# 2025_08_22_io.net
KiCad netlist of a schematic drawn in EasyEDA Pro
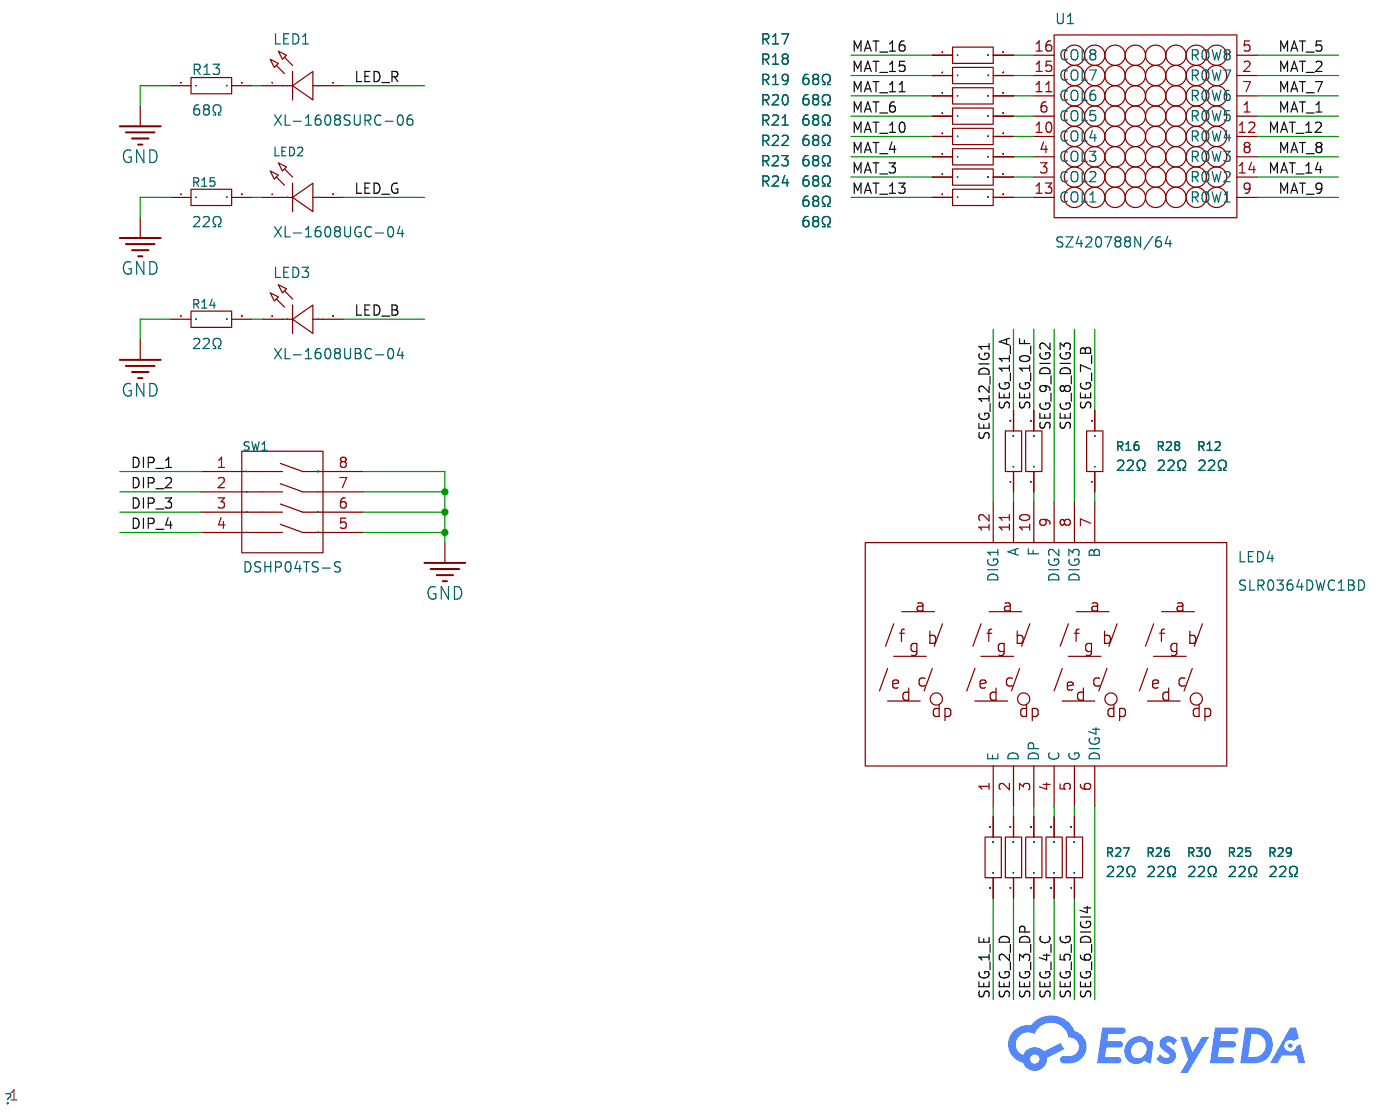
[diagram p0: schematic sheet]

(export (version "E")
  (design (tool "Eeschema 10.0.6"))
  (components
    (comp (ref "LED1")
      (value "XL-1608SURC-06")
      (footprint "easyedapro:LED0603-RD_RED")
      (fields (field (name "Manufacturer") "XINGLIGHT(成兴光)"))
      (libsource (lib "easyedapro") (part "XL-1608SURC-06"))
    )
    (comp (ref "LED2")
      (value "XL-1608UGC-04")
      (footprint "easyedapro:LED0603-RD_GREEN")
      (fields (field (name "Manufacturer") "XINGLIGHT(成兴光)"))
      (libsource (lib "easyedapro") (part "XL-1608UGC-04"))
    )
    (comp (ref "LED3")
      (value "XL-1608UBC-04")
      (footprint "easyedapro:LED0603-RD_BLUE")
      (fields (field (name "Manufacturer") "XINGLIGHT(成兴光)"))
      (libsource (lib "easyedapro") (part "XL-1608UBC-04"))
    )
    (comp (ref "LED4")
      (value "SLR0364DWC1BD")
      (footprint "easyedapro:LED-SEG-TH_12P-L30.0-W14.0-P2.54-S10.16-BL")
      (fields (field (name "Manufacturer") "SUNLIGHT(光华)"))
      (libsource (lib "easyedapro") (part "SLR0364DWC1BD_C2913068"))
    )
    (comp (ref "R12")
      (value "22Ω")
      (footprint "easyedapro:R0402")
      (fields
        (field (name "Manufacturer Part") "0402WGF220JTCE")
        (field (name "Manufacturer") "UNI-ROYAL(厚声)")
      )
      (libsource (lib "easyedapro") (part "0402WGF220JTCE"))
    )
    (comp (ref "R13")
      (value "68Ω")
      (footprint "easyedapro:R0402")
      (fields (field (name "Manufacturer Part") "RC0402FR-0768RL") (field (name "Manufacturer") "YAGEO(国巨)"))
      (libsource (lib "easyedapro") (part "RC0402FR-0768RL"))
    )
    (comp (ref "R14")
      (value "22Ω")
      (footprint "easyedapro:R0402")
      (fields
        (field (name "Manufacturer Part") "0402WGF220JTCE")
        (field (name "Manufacturer") "UNI-ROYAL(厚声)")
      )
      (libsource (lib "easyedapro") (part "0402WGF220JTCE"))
    )
    (comp (ref "R15")
      (value "22Ω")
      (footprint "easyedapro:R0402")
      (fields
        (field (name "Manufacturer Part") "0402WGF220JTCE")
        (field (name "Manufacturer") "UNI-ROYAL(厚声)")
      )
      (libsource (lib "easyedapro") (part "0402WGF220JTCE"))
    )
    (comp (ref "R16")
      (value "22Ω")
      (footprint "easyedapro:R0402")
      (fields
        (field (name "Manufacturer Part") "0402WGF220JTCE")
        (field (name "Manufacturer") "UNI-ROYAL(厚声)")
      )
      (libsource (lib "easyedapro") (part "0402WGF220JTCE"))
    )
    (comp (ref "R17")
      (value "68Ω")
      (footprint "easyedapro:R0402")
      (fields (field (name "Manufacturer Part") "RC0402FR-0768RL") (field (name "Manufacturer") "YAGEO(国巨)"))
      (libsource (lib "easyedapro") (part "RC0402FR-0768RL"))
    )
    (comp (ref "R18")
      (value "68Ω")
      (footprint "easyedapro:R0402")
      (fields (field (name "Manufacturer Part") "RC0402FR-0768RL") (field (name "Manufacturer") "YAGEO(国巨)"))
      (libsource (lib "easyedapro") (part "RC0402FR-0768RL"))
    )
    (comp (ref "R19")
      (value "68Ω")
      (footprint "easyedapro:R0402")
      (fields (field (name "Manufacturer Part") "RC0402FR-0768RL") (field (name "Manufacturer") "YAGEO(国巨)"))
      (libsource (lib "easyedapro") (part "RC0402FR-0768RL"))
    )
    (comp (ref "R20")
      (value "68Ω")
      (footprint "easyedapro:R0402")
      (fields (field (name "Manufacturer Part") "RC0402FR-0768RL") (field (name "Manufacturer") "YAGEO(国巨)"))
      (libsource (lib "easyedapro") (part "RC0402FR-0768RL"))
    )
    (comp (ref "R21")
      (value "68Ω")
      (footprint "easyedapro:R0402")
      (fields (field (name "Manufacturer Part") "RC0402FR-0768RL") (field (name "Manufacturer") "YAGEO(国巨)"))
      (libsource (lib "easyedapro") (part "RC0402FR-0768RL"))
    )
    (comp (ref "R22")
      (value "68Ω")
      (footprint "easyedapro:R0402")
      (fields (field (name "Manufacturer Part") "RC0402FR-0768RL") (field (name "Manufacturer") "YAGEO(国巨)"))
      (libsource (lib "easyedapro") (part "RC0402FR-0768RL"))
    )
    (comp (ref "R23")
      (value "68Ω")
      (footprint "easyedapro:R0402")
      (fields (field (name "Manufacturer Part") "RC0402FR-0768RL") (field (name "Manufacturer") "YAGEO(国巨)"))
      (libsource (lib "easyedapro") (part "RC0402FR-0768RL"))
    )
    (comp (ref "R24")
      (value "68Ω")
      (footprint "easyedapro:R0402")
      (fields (field (name "Manufacturer Part") "RC0402FR-0768RL") (field (name "Manufacturer") "YAGEO(国巨)"))
      (libsource (lib "easyedapro") (part "RC0402FR-0768RL"))
    )
    (comp (ref "R25")
      (value "22Ω")
      (footprint "easyedapro:R0402")
      (fields
        (field (name "Manufacturer Part") "0402WGF220JTCE")
        (field (name "Manufacturer") "UNI-ROYAL(厚声)")
      )
      (libsource (lib "easyedapro") (part "0402WGF220JTCE"))
    )
    (comp (ref "R26")
      (value "22Ω")
      (footprint "easyedapro:R0402")
      (fields
        (field (name "Manufacturer Part") "0402WGF220JTCE")
        (field (name "Manufacturer") "UNI-ROYAL(厚声)")
      )
      (libsource (lib "easyedapro") (part "0402WGF220JTCE"))
    )
    (comp (ref "R27")
      (value "22Ω")
      (footprint "easyedapro:R0402")
      (fields
        (field (name "Manufacturer Part") "0402WGF220JTCE")
        (field (name "Manufacturer") "UNI-ROYAL(厚声)")
      )
      (libsource (lib "easyedapro") (part "0402WGF220JTCE"))
    )
    (comp (ref "R28")
      (value "22Ω")
      (footprint "easyedapro:R0402")
      (fields
        (field (name "Manufacturer Part") "0402WGF220JTCE")
        (field (name "Manufacturer") "UNI-ROYAL(厚声)")
      )
      (libsource (lib "easyedapro") (part "0402WGF220JTCE"))
    )
    (comp (ref "R29")
      (value "22Ω")
      (footprint "easyedapro:R0402")
      (fields
        (field (name "Manufacturer Part") "0402WGF220JTCE")
        (field (name "Manufacturer") "UNI-ROYAL(厚声)")
      )
      (libsource (lib "easyedapro") (part "0402WGF220JTCE"))
    )
    (comp (ref "R30")
      (value "22Ω")
      (footprint "easyedapro:R0402")
      (fields
        (field (name "Manufacturer Part") "0402WGF220JTCE")
        (field (name "Manufacturer") "UNI-ROYAL(厚声)")
      )
      (libsource (lib "easyedapro") (part "0402WGF220JTCE"))
    )
    (comp (ref "SW1")
      (value "DSHP04TS-S")
      (footprint "easyedapro:SW-SMD_8P-L6.7-W5.4-P1.27-LS8.5")
      (fields (field (name "Manufacturer") "XKB Connectivity(中国星坤)"))
      (libsource (lib "easyedapro") (part "DSHP04TS-S"))
    )
    (comp (ref "U1")
      (value "SZ420788N/64")
      (footprint "easyedapro:LED-SEG-TH_SZ420788N-64")
      (description "Dot Matrix Number:8x8 Emitting Color:Red Polarity:Common Cathode")
      (fields (field (name "Manufacturer") "ARKLED(方舟)"))
      (libsource (lib "easyedapro") (part "SZ420788N/64"))
    )
  )
  (nets
    (net (code "1") (name "/DIP_1") (class "Default")
      (node (ref "SW1") (pin "1") (pinfunction "1_1") (pintype "input"))
    )
    (net (code "2") (name "/DIP_2") (class "Default")
      (node (ref "SW1") (pin "2") (pinfunction "2_2") (pintype "input"))
    )
    (net (code "3") (name "/DIP_3") (class "Default")
      (node (ref "SW1") (pin "3") (pinfunction "3_3") (pintype "input"))
    )
    (net (code "4") (name "/DIP_4") (class "Default")
      (node (ref "SW1") (pin "4") (pinfunction "4_4") (pintype "input"))
    )
    (net (code "5") (name "/LED_B") (class "Default")
      (node (ref "LED3") (pin "2") (pinfunction "A_2") (pintype "unspecified"))
    )
    (net (code "6") (name "/LED_G") (class "Default")
      (node (ref "LED2") (pin "2") (pinfunction "A_2") (pintype "input"))
    )
    (net (code "7") (name "/LED_R") (class "Default")
      (node (ref "LED1") (pin "2") (pinfunction "A_2") (pintype "unspecified"))
    )
    (net (code "8") (name "/MAT_1") (class "Default")
      (node (ref "U1") (pin "1") (pinfunction "ROW5_1") (pintype "unspecified"))
    )
    (net (code "9") (name "/MAT_2") (class "Default")
      (node (ref "U1") (pin "2") (pinfunction "ROW7_2") (pintype "unspecified"))
    )
    (net (code "10") (name "/MAT_3") (class "Default")
      (node (ref "R23") (pin "1") (pinfunction "1_1") (pintype "input"))
    )
    (net (code "11") (name "/MAT_4") (class "Default")
      (node (ref "R22") (pin "1") (pinfunction "1_1") (pintype "input"))
    )
    (net (code "12") (name "/MAT_5") (class "Default")
      (node (ref "U1") (pin "5") (pinfunction "ROW8_5") (pintype "unspecified"))
    )
    (net (code "13") (name "/MAT_6") (class "Default")
      (node (ref "R20") (pin "1") (pinfunction "1_1") (pintype "input"))
    )
    (net (code "14") (name "/MAT_7") (class "Default")
      (node (ref "U1") (pin "7") (pinfunction "ROW6_7") (pintype "unspecified"))
    )
    (net (code "15") (name "/MAT_8") (class "Default")
      (node (ref "U1") (pin "8") (pinfunction "ROW3_8") (pintype "unspecified"))
    )
    (net (code "16") (name "/MAT_9") (class "Default")
      (node (ref "U1") (pin "9") (pinfunction "ROW1_9") (pintype "unspecified"))
    )
    (net (code "17") (name "/MAT_10") (class "Default")
      (node (ref "R21") (pin "1") (pinfunction "1_1") (pintype "input"))
    )
    (net (code "18") (name "/MAT_11") (class "Default")
      (node (ref "R19") (pin "1") (pinfunction "1_1") (pintype "input"))
    )
    (net (code "19") (name "/MAT_12") (class "Default")
      (node (ref "U1") (pin "12") (pinfunction "ROW4_12") (pintype "unspecified"))
    )
    (net (code "20") (name "/MAT_13") (class "Default")
      (node (ref "R24") (pin "1") (pinfunction "1_1") (pintype "input"))
    )
    (net (code "21") (name "/MAT_14") (class "Default")
      (node (ref "U1") (pin "14") (pinfunction "ROW2_14") (pintype "unspecified"))
    )
    (net (code "22") (name "/MAT_15") (class "Default")
      (node (ref "R18") (pin "1") (pinfunction "1_1") (pintype "input"))
    )
    (net (code "23") (name "/MAT_16") (class "Default")
      (node (ref "R17") (pin "1") (pinfunction "1_1") (pintype "input"))
    )
    (net (code "24") (name "/SEG_1_E") (class "Default")
      (node (ref "R27") (pin "1") (pinfunction "1_1") (pintype "input"))
    )
    (net (code "25") (name "/SEG_2_D") (class "Default")
      (node (ref "R26") (pin "1") (pinfunction "1_1") (pintype "input"))
    )
    (net (code "26") (name "/SEG_3_DP") (class "Default")
      (node (ref "R30") (pin "1") (pinfunction "1_1") (pintype "input"))
    )
    (net (code "27") (name "/SEG_4_C") (class "Default")
      (node (ref "R25") (pin "1") (pinfunction "1_1") (pintype "input"))
    )
    (net (code "28") (name "/SEG_5_G") (class "Default")
      (node (ref "R29") (pin "1") (pinfunction "1_1") (pintype "input"))
    )
    (net (code "29") (name "/SEG_6_DIGI4") (class "Default")
      (node (ref "LED4") (pin "6") (pinfunction "DIG4_6") (pintype "input"))
    )
    (net (code "30") (name "/SEG_7_B") (class "Default")
      (node (ref "R12") (pin "2") (pinfunction "2_2") (pintype "input"))
    )
    (net (code "31") (name "/SEG_8_DIG3") (class "Default")
      (node (ref "LED4") (pin "8") (pinfunction "DIG3_8") (pintype "input"))
    )
    (net (code "32") (name "/SEG_9_DIG2") (class "Default")
      (node (ref "LED4") (pin "9") (pinfunction "DIG2_9") (pintype "input"))
    )
    (net (code "33") (name "/SEG_10_F") (class "Default")
      (node (ref "R28") (pin "2") (pinfunction "2_2") (pintype "input"))
    )
    (net (code "34") (name "/SEG_11_A") (class "Default")
      (node (ref "R16") (pin "2") (pinfunction "2_2") (pintype "input"))
    )
    (net (code "35") (name "/SEG_12_DIG1") (class "Default")
      (node (ref "LED4") (pin "12") (pinfunction "DIG1_12") (pintype "input"))
    )
    (net (code "36") (name "GND") (class "Default")
      (node (ref "R13") (pin "1") (pinfunction "1_1") (pintype "input"))
      (node (ref "R14") (pin "1") (pinfunction "1_1") (pintype "input"))
      (node (ref "R15") (pin "1") (pinfunction "1_1") (pintype "input"))
      (node (ref "SW1") (pin "5") (pinfunction "5_5") (pintype "input"))
      (node (ref "SW1") (pin "6") (pinfunction "6_6") (pintype "input"))
      (node (ref "SW1") (pin "7") (pinfunction "7_7") (pintype "input"))
      (node (ref "SW1") (pin "8") (pinfunction "8_8") (pintype "input"))
    )
    (net (code "37") (name "Net-(LED1-K)") (class "Default")
      (node (ref "LED1") (pin "1") (pinfunction "K_1") (pintype "unspecified"))
      (node (ref "R13") (pin "2") (pinfunction "2_2") (pintype "input"))
    )
    (net (code "38") (name "Net-(LED2-K)") (class "Default")
      (node (ref "LED2") (pin "1") (pinfunction "K_1") (pintype "input"))
      (node (ref "R15") (pin "2") (pinfunction "2_2") (pintype "input"))
    )
    (net (code "39") (name "Net-(LED3-K)") (class "Default")
      (node (ref "LED3") (pin "1") (pinfunction "K_1") (pintype "unspecified"))
      (node (ref "R14") (pin "2") (pinfunction "2_2") (pintype "input"))
    )
    (net (code "40") (name "Net-(LED4-A)") (class "Default")
      (node (ref "LED4") (pin "11") (pinfunction "A_11") (pintype "input"))
      (node (ref "R16") (pin "1") (pinfunction "1_1") (pintype "input"))
    )
    (net (code "41") (name "Net-(LED4-B)") (class "Default")
      (node (ref "LED4") (pin "7") (pinfunction "B_7") (pintype "input"))
      (node (ref "R12") (pin "1") (pinfunction "1_1") (pintype "input"))
    )
    (net (code "42") (name "Net-(LED4-C)") (class "Default")
      (node (ref "LED4") (pin "4") (pinfunction "C_4") (pintype "input"))
      (node (ref "R25") (pin "2") (pinfunction "2_2") (pintype "input"))
    )
    (net (code "43") (name "Net-(LED4-D)") (class "Default")
      (node (ref "LED4") (pin "2") (pinfunction "D_2") (pintype "input"))
      (node (ref "R26") (pin "2") (pinfunction "2_2") (pintype "input"))
    )
    (net (code "44") (name "Net-(LED4-DP)") (class "Default")
      (node (ref "LED4") (pin "3") (pinfunction "DP_3") (pintype "input"))
      (node (ref "R30") (pin "2") (pinfunction "2_2") (pintype "input"))
    )
    (net (code "45") (name "Net-(LED4-E)") (class "Default")
      (node (ref "LED4") (pin "1") (pinfunction "E_1") (pintype "input"))
      (node (ref "R27") (pin "2") (pinfunction "2_2") (pintype "input"))
    )
    (net (code "46") (name "Net-(LED4-F)") (class "Default")
      (node (ref "LED4") (pin "10") (pinfunction "F_10") (pintype "input"))
      (node (ref "R28") (pin "1") (pinfunction "1_1") (pintype "input"))
    )
    (net (code "47") (name "Net-(LED4-G)") (class "Default")
      (node (ref "LED4") (pin "5") (pinfunction "G_5") (pintype "input"))
      (node (ref "R29") (pin "2") (pinfunction "2_2") (pintype "input"))
    )
    (net (code "48") (name "Net-(U1-COL1)") (class "Default")
      (node (ref "R24") (pin "2") (pinfunction "2_2") (pintype "input"))
      (node (ref "U1") (pin "13") (pinfunction "COL1_13") (pintype "unspecified"))
    )
    (net (code "49") (name "Net-(U1-COL2)") (class "Default")
      (node (ref "R23") (pin "2") (pinfunction "2_2") (pintype "input"))
      (node (ref "U1") (pin "3") (pinfunction "COL2_3") (pintype "unspecified"))
    )
    (net (code "50") (name "Net-(U1-COL3)") (class "Default")
      (node (ref "R22") (pin "2") (pinfunction "2_2") (pintype "input"))
      (node (ref "U1") (pin "4") (pinfunction "COL3_4") (pintype "unspecified"))
    )
    (net (code "51") (name "Net-(U1-COL4)") (class "Default")
      (node (ref "R21") (pin "2") (pinfunction "2_2") (pintype "input"))
      (node (ref "U1") (pin "10") (pinfunction "COL4_10") (pintype "unspecified"))
    )
    (net (code "52") (name "Net-(U1-COL5)") (class "Default")
      (node (ref "R20") (pin "2") (pinfunction "2_2") (pintype "input"))
      (node (ref "U1") (pin "6") (pinfunction "COL5_6") (pintype "unspecified"))
    )
    (net (code "53") (name "Net-(U1-COL6)") (class "Default")
      (node (ref "R19") (pin "2") (pinfunction "2_2") (pintype "input"))
      (node (ref "U1") (pin "11") (pinfunction "COL6_11") (pintype "unspecified"))
    )
    (net (code "54") (name "Net-(U1-COL7)") (class "Default")
      (node (ref "R18") (pin "2") (pinfunction "2_2") (pintype "input"))
      (node (ref "U1") (pin "15") (pinfunction "COL7_15") (pintype "unspecified"))
    )
    (net (code "55") (name "Net-(U1-COL8)") (class "Default")
      (node (ref "R17") (pin "2") (pinfunction "2_2") (pintype "input"))
      (node (ref "U1") (pin "16") (pinfunction "COL8_16") (pintype "unspecified"))
    )
  )
)
